# wt11i_uart_breakout_board_v21.net
KiCad netlist of a schematic drawn in EAGLE
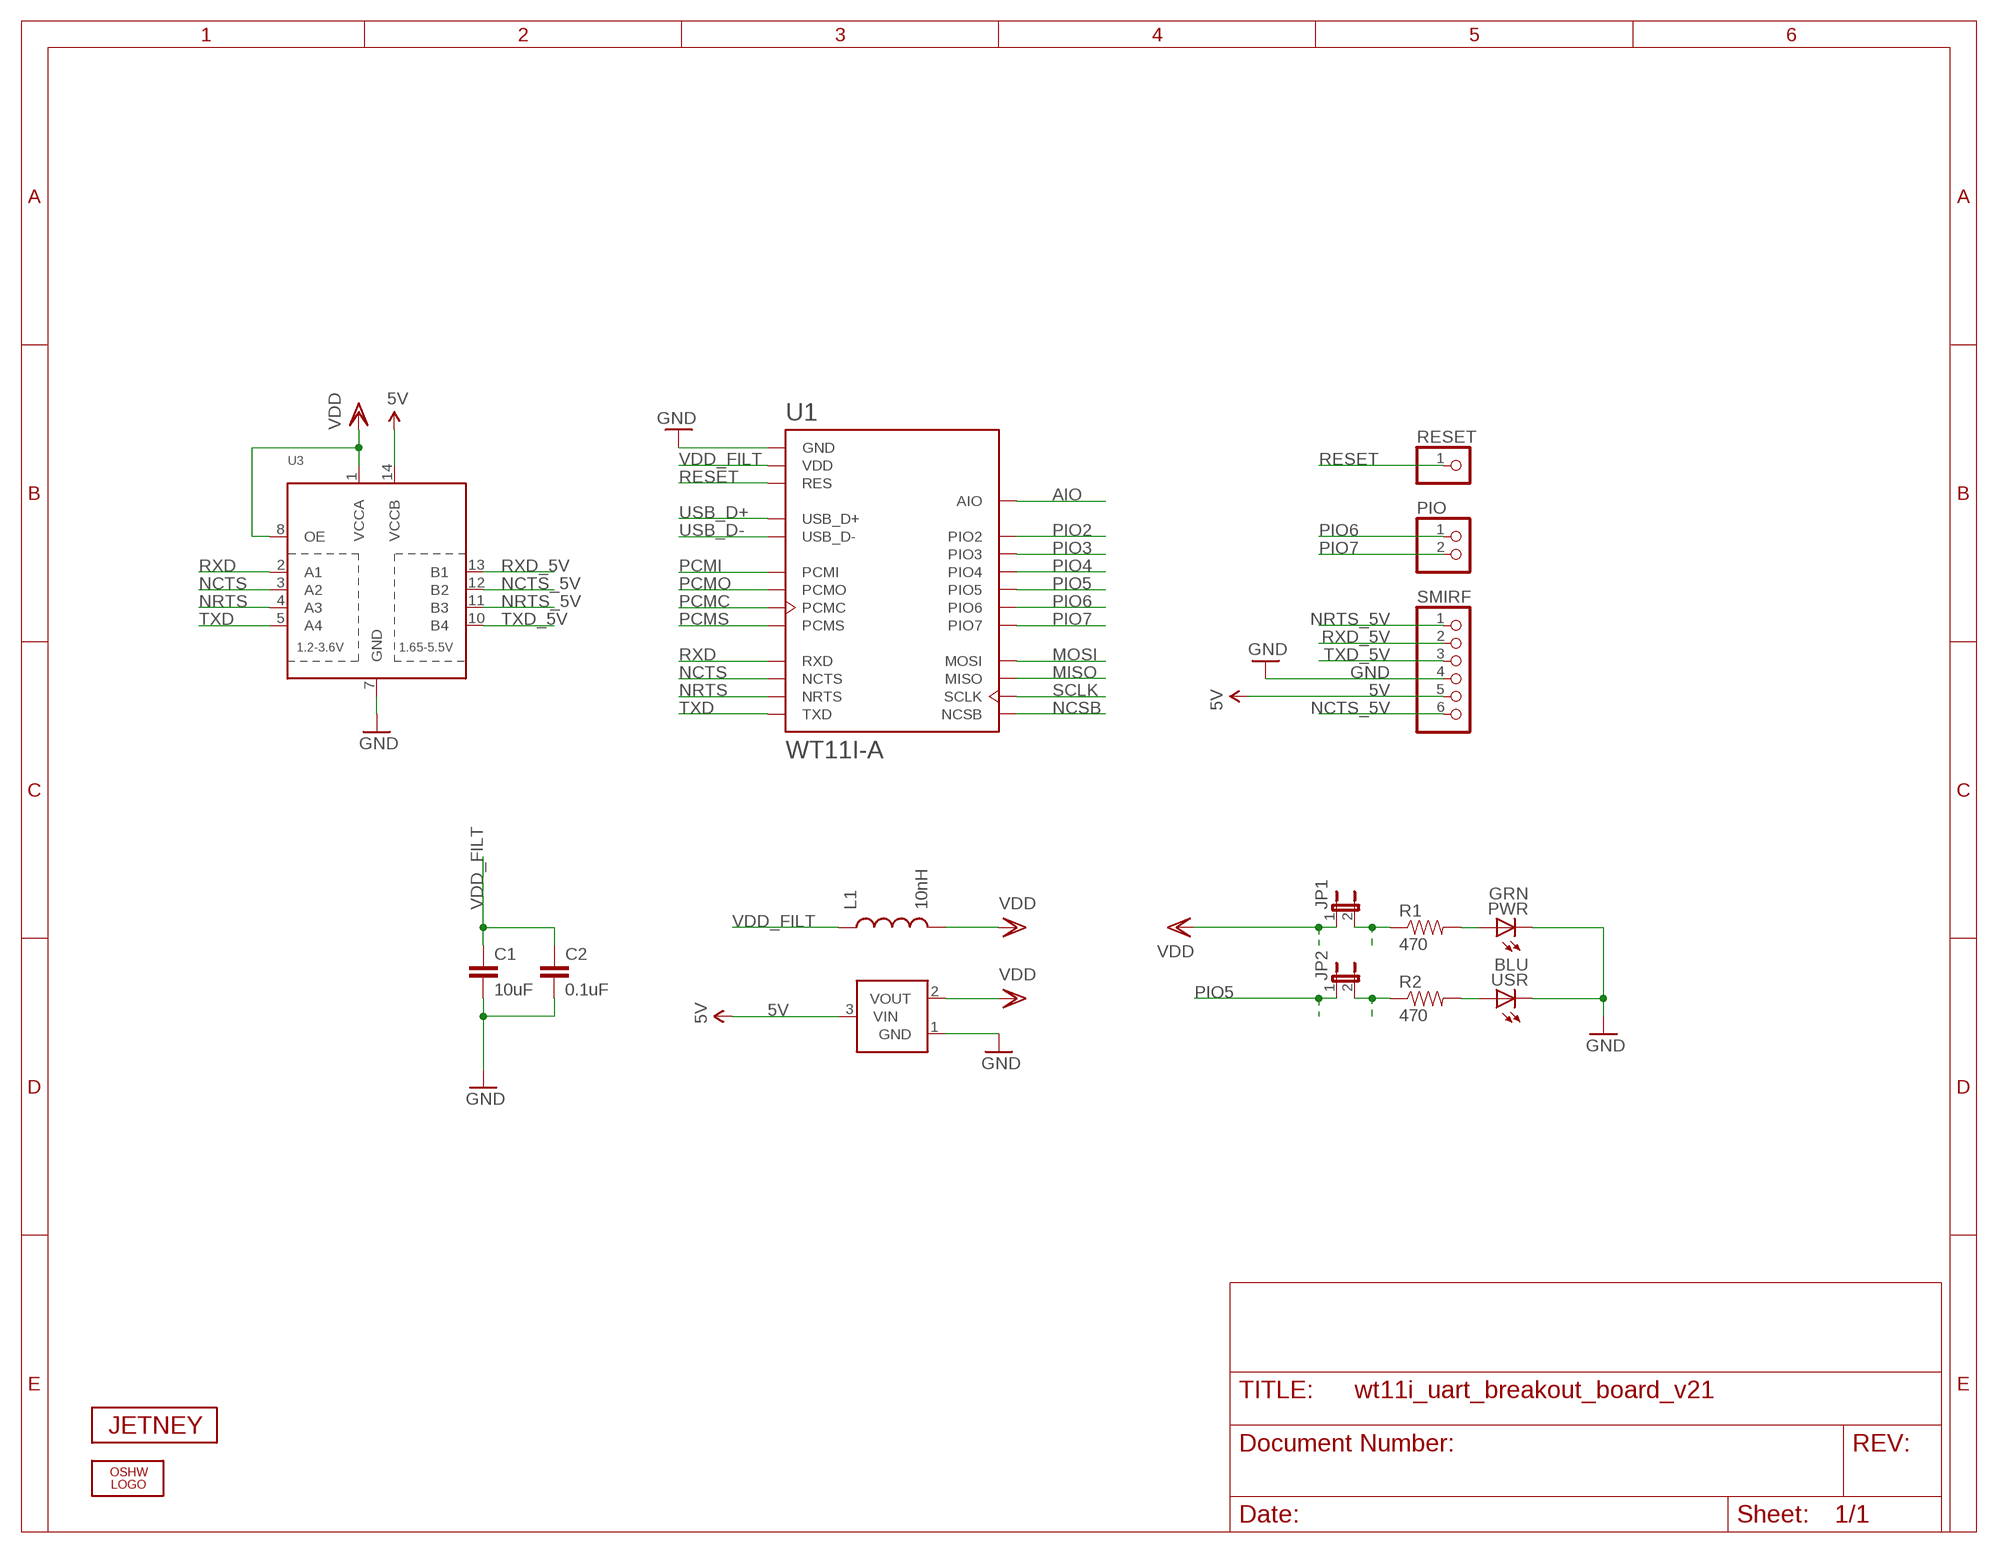
[diagram p0: schematic, sheet 1]

(export (version "E")
  (design (tool "Eeschema 10.0.6"))
  (components
    (comp (ref "C1")
      (value "10uF")
      (footprint "eagle-import:0603-CAP")
      (libsource (lib "eagle-import") (part "CAP0603-CAP"))
    )
    (comp (ref "C2")
      (value "0.1uF")
      (footprint "eagle-import:0603-CAP")
      (libsource (lib "eagle-import") (part "CAP0603-CAP"))
    )
    (comp (ref "JP1")
      (value "JUMPER-2SMD-NC")
      (footprint "eagle-import:SJ_2S")
      (libsource (lib "eagle-import") (part "JUMPER-2SMD-NC"))
    )
    (comp (ref "JP2")
      (value "JUMPER-2SMD-NC")
      (footprint "eagle-import:SJ_2S")
      (libsource (lib "eagle-import") (part "JUMPER-2SMD-NC"))
    )
    (comp (ref "L1")
      (value "10nH")
      (footprint "eagle-import:0603")
      (libsource (lib "eagle-import") (part "INDUCTOR0603"))
    )
    (comp (ref "LOGO1")
      (value "OSHW_LOGO_FILLX0070-NT")
      (footprint "eagle-import:OSHW_FILLX70_NOTEXT")
      (libsource (lib "eagle-import") (part "OSHW_LOGO_FILLX0070-NT"))
    )
    (comp (ref "PIO")
      (value "PINHD-1X2")
      (footprint "eagle-import:1X02")
      (libsource (lib "eagle-import") (part "PINHD-1X2"))
    )
    (comp (ref "PWR")
      (value "GRN")
      (footprint "eagle-import:CHIPLED_0805")
      (libsource (lib "eagle-import") (part "LEDCHIPLED_0805"))
    )
    (comp (ref "R1")
      (value "470")
      (footprint "eagle-import:0603-RES")
      (libsource (lib "eagle-import") (part "RESISTOR0603-RES"))
    )
    (comp (ref "R2")
      (value "470")
      (footprint "eagle-import:0603-RES")
      (libsource (lib "eagle-import") (part "RESISTOR0603-RES"))
    )
    (comp (ref "RESET")
      (value "PINHD-1X1")
      (footprint "eagle-import:1X01")
      (libsource (lib "eagle-import") (part "PINHD-1X1"))
    )
    (comp (ref "SMIRF")
      (value "PINHD-1X6")
      (footprint "eagle-import:1X06")
      (libsource (lib "eagle-import") (part "PINHD-1X6"))
    )
    (comp (ref "U$4")
      (value "JETNEY-LOGO-12")
      (footprint "eagle-import:JETNEY-LOGO-12")
      (libsource (lib "eagle-import") (part "JETNEY-LOGO-12"))
    )
    (comp (ref "U1")
      (value "WT11I-A")
      (footprint "eagle-import:WT11I-A")
      (libsource (lib "eagle-import") (part "WT11I-A"))
    )
    (comp (ref "U2")
      (value "MCP1700")
      (footprint "eagle-import:SOT23-3")
      (libsource (lib "eagle-import") (part "MCP1700"))
    )
    (comp (ref "U3")
      (value "TXB0104PWR")
      (footprint "eagle-import:TSSOP14")
      (libsource (lib "eagle-import") (part "TXB0104PWR"))
    )
    (comp (ref "USR")
      (value "BLU")
      (footprint "eagle-import:CHIPLED_0805")
      (libsource (lib "eagle-import") (part "LEDCHIPLED_0805"))
    )
  )
  (nets
    (net (code "1") (name "/AIO") (class "Default")
      (node (ref "U1") (pin "AIO") (pinfunction "AIO_AIO") (pintype "bidirectional"))
    )
    (net (code "2") (name "/MISO") (class "Default")
      (node (ref "U1") (pin "MISO") (pinfunction "MISO_MISO") (pintype "output"))
    )
    (net (code "3") (name "/MOSI") (class "Default")
      (node (ref "U1") (pin "MOSI") (pinfunction "MOSI_MOSI") (pintype "input"))
    )
    (net (code "4") (name "/NCSB") (class "Default")
      (node (ref "U1") (pin "NCSB") (pinfunction "NCSB_NCSB") (pintype "input"))
    )
    (net (code "5") (name "/NCTS") (class "Default")
      (node (ref "U1") (pin "NCTS") (pinfunction "NCTS_NCTS") (pintype "input"))
      (node (ref "U3") (pin "3") (pinfunction "A2_3") (pintype "bidirectional"))
    )
    (net (code "6") (name "/NCTS_5V") (class "Default")
      (node (ref "SMIRF") (pin "6") (pinfunction "6_6") (pintype "passive"))
      (node (ref "U3") (pin "12") (pinfunction "B2_12") (pintype "bidirectional"))
    )
    (net (code "7") (name "/NRTS") (class "Default")
      (node (ref "U1") (pin "NRTS") (pinfunction "NRTS_NRTS") (pintype "output"))
      (node (ref "U3") (pin "4") (pinfunction "A3_4") (pintype "bidirectional"))
    )
    (net (code "8") (name "/NRTS_5V") (class "Default")
      (node (ref "SMIRF") (pin "1") (pinfunction "1_1") (pintype "passive"))
      (node (ref "U3") (pin "11") (pinfunction "B3_11") (pintype "bidirectional"))
    )
    (net (code "9") (name "/PCMC") (class "Default")
      (node (ref "U1") (pin "PCMC") (pinfunction "PCMC_PCMC") (pintype "bidirectional"))
    )
    (net (code "10") (name "/PCMI") (class "Default")
      (node (ref "U1") (pin "PCMI") (pinfunction "PCMI_PCMI") (pintype "input"))
    )
    (net (code "11") (name "/PCMO") (class "Default")
      (node (ref "U1") (pin "PCMO") (pinfunction "PCMO_PCMO") (pintype "output"))
    )
    (net (code "12") (name "/PCMS") (class "Default")
      (node (ref "U1") (pin "PCMS") (pinfunction "PCMS_PCMS") (pintype "bidirectional"))
    )
    (net (code "13") (name "/PIO2") (class "Default")
      (node (ref "U1") (pin "PIO2") (pinfunction "PIO2_PIO2") (pintype "bidirectional"))
    )
    (net (code "14") (name "/PIO3") (class "Default")
      (node (ref "U1") (pin "PIO3") (pinfunction "PIO3_PIO3") (pintype "bidirectional"))
    )
    (net (code "15") (name "/PIO4") (class "Default")
      (node (ref "U1") (pin "PIO4") (pinfunction "PIO4_PIO4") (pintype "bidirectional"))
    )
    (net (code "16") (name "/PIO5") (class "Default")
      (node (ref "JP2") (pin "1") (pinfunction "1_1") (pintype "passive"))
      (node (ref "U1") (pin "PIO5") (pinfunction "PIO5_PIO5") (pintype "bidirectional"))
    )
    (net (code "17") (name "/PIO6") (class "Default")
      (node (ref "PIO") (pin "1") (pinfunction "1_1") (pintype "passive"))
      (node (ref "U1") (pin "PIO6") (pinfunction "PIO6_PIO6") (pintype "bidirectional"))
    )
    (net (code "18") (name "/PIO7") (class "Default")
      (node (ref "PIO") (pin "2") (pinfunction "2_2") (pintype "passive"))
      (node (ref "U1") (pin "PIO7") (pinfunction "PIO7_PIO7") (pintype "bidirectional"))
    )
    (net (code "19") (name "/RESET") (class "Default")
      (node (ref "RESET") (pin "1") (pinfunction "1_1") (pintype "passive"))
      (node (ref "U1") (pin "RES") (pinfunction "RES_RES") (pintype "input"))
    )
    (net (code "20") (name "/RXD") (class "Default")
      (node (ref "U1") (pin "RXD") (pinfunction "RXD_RXD") (pintype "input"))
      (node (ref "U3") (pin "2") (pinfunction "A1_2") (pintype "bidirectional"))
    )
    (net (code "21") (name "/RXD_5V") (class "Default")
      (node (ref "SMIRF") (pin "2") (pinfunction "2_2") (pintype "passive"))
      (node (ref "U3") (pin "13") (pinfunction "B1_13") (pintype "bidirectional"))
    )
    (net (code "22") (name "/SCLK") (class "Default")
      (node (ref "U1") (pin "SCLK") (pinfunction "SCLK_SCLK") (pintype "input"))
    )
    (net (code "23") (name "/TXD") (class "Default")
      (node (ref "U1") (pin "TXD") (pinfunction "TXD_TXD") (pintype "output"))
      (node (ref "U3") (pin "5") (pinfunction "A4_5") (pintype "bidirectional"))
    )
    (net (code "24") (name "/TXD_5V") (class "Default")
      (node (ref "SMIRF") (pin "3") (pinfunction "3_3") (pintype "passive"))
      (node (ref "U3") (pin "10") (pinfunction "B4_10") (pintype "bidirectional"))
    )
    (net (code "25") (name "/USB_D+") (class "Default")
      (node (ref "U1") (pin "USB_D+") (pinfunction "USB_D+_USB_D+") (pintype "bidirectional"))
    )
    (net (code "26") (name "/USB_D-") (class "Default")
      (node (ref "U1") (pin "USB_D-") (pinfunction "USB_D-_USB_D-") (pintype "bidirectional"))
    )
    (net (code "27") (name "/VDD_FILT") (class "Default")
      (node (ref "C1") (pin "1") (pinfunction "1_1") (pintype "passive"))
      (node (ref "C2") (pin "1") (pinfunction "1_1") (pintype "passive"))
      (node (ref "L1") (pin "1") (pinfunction "1_1") (pintype "passive"))
      (node (ref "U1") (pin "VDD") (pinfunction "VDD_VDD") (pintype "power_in"))
      (node (ref "U1") (pin "VDD@2") (pinfunction "VDD_VDD@2") (pintype "power_in"))
    )
    (net (code "28") (name "5V") (class "Default")
      (node (ref "SMIRF") (pin "5") (pinfunction "5_5") (pintype "passive"))
      (node (ref "U2") (pin "3") (pinfunction "VIN_3") (pintype "power_in"))
      (node (ref "U3") (pin "14") (pinfunction "VCCB_14") (pintype "bidirectional"))
    )
    (net (code "29") (name "GND") (class "Default")
      (node (ref "C1") (pin "2") (pinfunction "2_2") (pintype "passive"))
      (node (ref "C2") (pin "2") (pinfunction "2_2") (pintype "passive"))
      (node (ref "PWR") (pin "C") (pinfunction "C_C") (pintype "passive"))
      (node (ref "SMIRF") (pin "4") (pinfunction "4_4") (pintype "passive"))
      (node (ref "U1") (pin "GND") (pinfunction "GND_GND") (pintype "power_in"))
      (node (ref "U1") (pin "GND@2") (pinfunction "GND_GND@2") (pintype "power_in"))
      (node (ref "U1") (pin "GND@3") (pinfunction "GND_GND@3") (pintype "power_in"))
      (node (ref "U1") (pin "GND@4") (pinfunction "GND_GND@4") (pintype "power_in"))
      (node (ref "U2") (pin "1") (pinfunction "GND_1") (pintype "power_in"))
      (node (ref "U3") (pin "7") (pinfunction "GND_7") (pintype "bidirectional"))
      (node (ref "USR") (pin "C") (pinfunction "C_C") (pintype "passive"))
    )
    (net (code "30") (name "Net-(JP1-Pad2)") (class "Default")
      (node (ref "JP1") (pin "2") (pinfunction "2_2") (pintype "passive"))
      (node (ref "R1") (pin "1") (pinfunction "1_1") (pintype "passive"))
    )
    (net (code "31") (name "Net-(JP2-Pad2)") (class "Default")
      (node (ref "JP2") (pin "2") (pinfunction "2_2") (pintype "passive"))
      (node (ref "R2") (pin "1") (pinfunction "1_1") (pintype "passive"))
    )
    (net (code "32") (name "Net-(PWR-PadA)") (class "Default")
      (node (ref "PWR") (pin "A") (pinfunction "A_A") (pintype "passive"))
      (node (ref "R1") (pin "2") (pinfunction "2_2") (pintype "passive"))
    )
    (net (code "33") (name "Net-(R2-Pad2)") (class "Default")
      (node (ref "R2") (pin "2") (pinfunction "2_2") (pintype "passive"))
      (node (ref "USR") (pin "A") (pinfunction "A_A") (pintype "passive"))
    )
    (net (code "34") (name "VDD") (class "Default")
      (node (ref "JP1") (pin "1") (pinfunction "1_1") (pintype "passive"))
      (node (ref "L1") (pin "2") (pinfunction "2_2") (pintype "passive"))
      (node (ref "U2") (pin "2") (pinfunction "VOUT_2") (pintype "power_in"))
      (node (ref "U3") (pin "1") (pinfunction "VCCA_1") (pintype "bidirectional"))
      (node (ref "U3") (pin "8") (pinfunction "OE_8") (pintype "bidirectional"))
    )
  )
)
